# jack_breakout.net
KiCad netlist of a schematic drawn in EAGLE
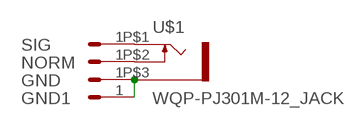
[diagram p0: schematic, sheet 1]

(export (version "E")
  (design (tool "Eeschema 10.0.6"))
  (components
    (comp (ref "GND")
      (value "HEADER/MALE/01")
      (footprint "eagle-import:HEADER_MALE_01")
      (libsource (lib "eagle-import") (part "HEADER/MALE/01"))
    )
    (comp (ref "GND1")
      (value "HEADER/MALE/01")
      (footprint "eagle-import:HEADER_MALE_01")
      (libsource (lib "eagle-import") (part "HEADER/MALE/01"))
    )
    (comp (ref "NORM")
      (value "HEADER/MALE/01")
      (footprint "eagle-import:HEADER_MALE_01")
      (libsource (lib "eagle-import") (part "HEADER/MALE/01"))
    )
    (comp (ref "SIG")
      (value "HEADER/MALE/01")
      (footprint "eagle-import:HEADER_MALE_01")
      (libsource (lib "eagle-import") (part "HEADER/MALE/01"))
    )
    (comp (ref "U$1")
      (value "WQP-PJ301M-12_JACK")
      (footprint "eagle-import:WQP-PJ301M-12_JACK")
      (libsource (lib "eagle-import") (part "WQP-PJ301M-12_JACK"))
    )
  )
  (nets
    (net (code "1") (name "Net-(GND-3)") (class "Default")
      (node (ref "GND") (pin "1") (pinfunction "3_1") (pintype "passive"))
      (node (ref "GND1") (pin "1") (pinfunction "3_1") (pintype "passive"))
      (node (ref "U$1") (pin "P$3") (pinfunction "1_P$3") (pintype "passive"))
    )
    (net (code "2") (name "Net-(NORM-3)") (class "Default")
      (node (ref "NORM") (pin "1") (pinfunction "3_1") (pintype "passive"))
      (node (ref "U$1") (pin "P$2") (pinfunction "3_P$2") (pintype "passive"))
    )
    (net (code "3") (name "Net-(SIG-3)") (class "Default")
      (node (ref "SIG") (pin "1") (pinfunction "3_1") (pintype "passive"))
      (node (ref "U$1") (pin "P$1") (pinfunction "2_P$1") (pintype "passive"))
    )
  )
)
